# M_A_jumper_bed.net
KiCad netlist of a schematic drawn in EAGLE
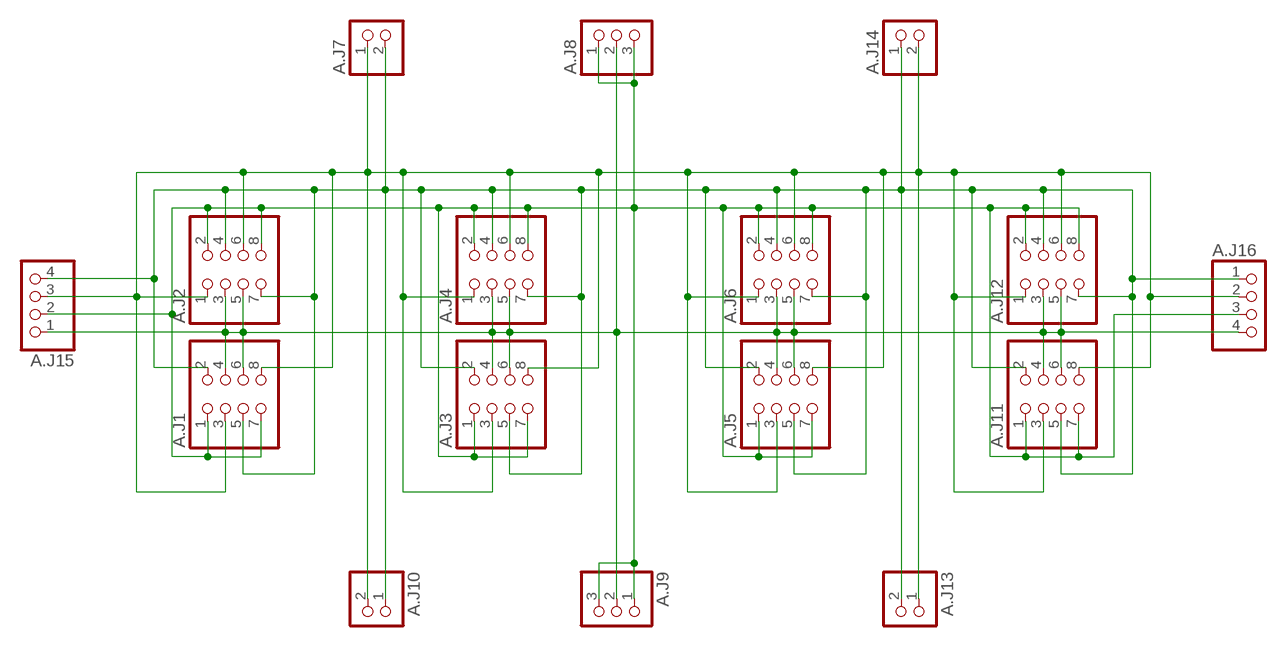
[diagram p0: schematic, sheet 1]

(export (version "E")
  (design (tool "Eeschema 10.0.6"))
  (components
    (comp (ref "A.J1")
      (value "PINHD-2X4")
      (footprint "eagle-import:2X04")
      (libsource (lib "eagle-import") (part "PINHD-2X4"))
    )
    (comp (ref "A.J2")
      (value "PINHD-2X4")
      (footprint "eagle-import:2X04")
      (libsource (lib "eagle-import") (part "PINHD-2X4"))
    )
    (comp (ref "A.J3")
      (value "PINHD-2X4")
      (footprint "eagle-import:2X04")
      (libsource (lib "eagle-import") (part "PINHD-2X4"))
    )
    (comp (ref "A.J4")
      (value "PINHD-2X4")
      (footprint "eagle-import:2X04")
      (libsource (lib "eagle-import") (part "PINHD-2X4"))
    )
    (comp (ref "A.J5")
      (value "PINHD-2X4")
      (footprint "eagle-import:2X04")
      (libsource (lib "eagle-import") (part "PINHD-2X4"))
    )
    (comp (ref "A.J6")
      (value "PINHD-2X4")
      (footprint "eagle-import:2X04")
      (libsource (lib "eagle-import") (part "PINHD-2X4"))
    )
    (comp (ref "A.J7")
      (value "PINHD-1X2/90")
      (footprint "eagle-import:1X02_90")
      (libsource (lib "eagle-import") (part "PINHD-1X2/90"))
    )
    (comp (ref "A.J8")
      (value "PINHD-1X3/90")
      (footprint "eagle-import:1X03_90")
      (libsource (lib "eagle-import") (part "PINHD-1X3/90"))
    )
    (comp (ref "A.J9")
      (value "PINHD-1X31X03/90F")
      (footprint "eagle-import:1X03_90F")
      (libsource (lib "eagle-import") (part "PINHD-1X31X03/90F"))
    )
    (comp (ref "A.J10")
      (value "PINHD-1X21X02/90F")
      (footprint "eagle-import:1X02_90F")
      (libsource (lib "eagle-import") (part "PINHD-1X21X02/90F"))
    )
    (comp (ref "A.J11")
      (value "PINHD-2X4")
      (footprint "eagle-import:2X04")
      (libsource (lib "eagle-import") (part "PINHD-2X4"))
    )
    (comp (ref "A.J12")
      (value "PINHD-2X4")
      (footprint "eagle-import:2X04")
      (libsource (lib "eagle-import") (part "PINHD-2X4"))
    )
    (comp (ref "A.J13")
      (value "PINHD-1X21X02/90F")
      (footprint "eagle-import:1X02_90F")
      (libsource (lib "eagle-import") (part "PINHD-1X21X02/90F"))
    )
    (comp (ref "A.J14")
      (value "PINHD-1X2/90")
      (footprint "eagle-import:1X02_90")
      (libsource (lib "eagle-import") (part "PINHD-1X2/90"))
    )
    (comp (ref "A.J15")
      (value "PINHD-1X4")
      (footprint "eagle-import:1X04")
      (libsource (lib "eagle-import") (part "PINHD-1X4"))
    )
    (comp (ref "A.J16")
      (value "PINHD-1X4")
      (footprint "eagle-import:1X04")
      (libsource (lib "eagle-import") (part "PINHD-1X4"))
    )
  )
  (nets
    (net (code "1") (name "Net-(A.J1-Pad1)") (class "Default")
      (node (ref "A.J1") (pin "1") (pinfunction "1_1") (pintype "passive"))
      (node (ref "A.J1") (pin "7") (pinfunction "7_7") (pintype "passive"))
      (node (ref "A.J11") (pin "1") (pinfunction "1_1") (pintype "passive"))
      (node (ref "A.J11") (pin "7") (pinfunction "7_7") (pintype "passive"))
      (node (ref "A.J12") (pin "2") (pinfunction "2_2") (pintype "passive"))
      (node (ref "A.J12") (pin "8") (pinfunction "8_8") (pintype "passive"))
      (node (ref "A.J15") (pin "2") (pinfunction "2_2") (pintype "passive"))
      (node (ref "A.J16") (pin "3") (pinfunction "3_3") (pintype "passive"))
      (node (ref "A.J2") (pin "2") (pinfunction "2_2") (pintype "passive"))
      (node (ref "A.J2") (pin "8") (pinfunction "8_8") (pintype "passive"))
      (node (ref "A.J3") (pin "1") (pinfunction "1_1") (pintype "passive"))
      (node (ref "A.J3") (pin "7") (pinfunction "7_7") (pintype "passive"))
      (node (ref "A.J4") (pin "2") (pinfunction "2_2") (pintype "passive"))
      (node (ref "A.J4") (pin "8") (pinfunction "8_8") (pintype "passive"))
      (node (ref "A.J5") (pin "1") (pinfunction "1_1") (pintype "passive"))
      (node (ref "A.J5") (pin "7") (pinfunction "7_7") (pintype "passive"))
      (node (ref "A.J6") (pin "2") (pinfunction "2_2") (pintype "passive"))
      (node (ref "A.J6") (pin "8") (pinfunction "8_8") (pintype "passive"))
      (node (ref "A.J8") (pin "1") (pinfunction "1_1") (pintype "passive"))
      (node (ref "A.J8") (pin "3") (pinfunction "3_3") (pintype "passive"))
      (node (ref "A.J9") (pin "1") (pinfunction "1_1") (pintype "passive"))
      (node (ref "A.J9") (pin "3") (pinfunction "3_3") (pintype "passive"))
    )
    (net (code "2") (name "Net-(A.J1-Pad2)") (class "Default")
      (node (ref "A.J1") (pin "2") (pinfunction "2_2") (pintype "passive"))
      (node (ref "A.J1") (pin "5") (pinfunction "5_5") (pintype "passive"))
      (node (ref "A.J10") (pin "1") (pinfunction "1_1") (pintype "passive"))
      (node (ref "A.J11") (pin "2") (pinfunction "2_2") (pintype "passive"))
      (node (ref "A.J11") (pin "5") (pinfunction "5_5") (pintype "passive"))
      (node (ref "A.J12") (pin "4") (pinfunction "4_4") (pintype "passive"))
      (node (ref "A.J12") (pin "7") (pinfunction "7_7") (pintype "passive"))
      (node (ref "A.J13") (pin "2") (pinfunction "2_2") (pintype "passive"))
      (node (ref "A.J14") (pin "1") (pinfunction "1_1") (pintype "passive"))
      (node (ref "A.J15") (pin "4") (pinfunction "4_4") (pintype "passive"))
      (node (ref "A.J16") (pin "1") (pinfunction "1_1") (pintype "passive"))
      (node (ref "A.J2") (pin "4") (pinfunction "4_4") (pintype "passive"))
      (node (ref "A.J2") (pin "7") (pinfunction "7_7") (pintype "passive"))
      (node (ref "A.J3") (pin "2") (pinfunction "2_2") (pintype "passive"))
      (node (ref "A.J3") (pin "5") (pinfunction "5_5") (pintype "passive"))
      (node (ref "A.J4") (pin "4") (pinfunction "4_4") (pintype "passive"))
      (node (ref "A.J4") (pin "7") (pinfunction "7_7") (pintype "passive"))
      (node (ref "A.J5") (pin "2") (pinfunction "2_2") (pintype "passive"))
      (node (ref "A.J5") (pin "5") (pinfunction "5_5") (pintype "passive"))
      (node (ref "A.J6") (pin "4") (pinfunction "4_4") (pintype "passive"))
      (node (ref "A.J6") (pin "7") (pinfunction "7_7") (pintype "passive"))
      (node (ref "A.J7") (pin "2") (pinfunction "2_2") (pintype "passive"))
    )
    (net (code "3") (name "Net-(A.J1-Pad3)") (class "Default")
      (node (ref "A.J1") (pin "3") (pinfunction "3_3") (pintype "passive"))
      (node (ref "A.J1") (pin "8") (pinfunction "8_8") (pintype "passive"))
      (node (ref "A.J10") (pin "2") (pinfunction "2_2") (pintype "passive"))
      (node (ref "A.J11") (pin "3") (pinfunction "3_3") (pintype "passive"))
      (node (ref "A.J11") (pin "8") (pinfunction "8_8") (pintype "passive"))
      (node (ref "A.J12") (pin "1") (pinfunction "1_1") (pintype "passive"))
      (node (ref "A.J12") (pin "6") (pinfunction "6_6") (pintype "passive"))
      (node (ref "A.J13") (pin "1") (pinfunction "1_1") (pintype "passive"))
      (node (ref "A.J14") (pin "2") (pinfunction "2_2") (pintype "passive"))
      (node (ref "A.J15") (pin "3") (pinfunction "3_3") (pintype "passive"))
      (node (ref "A.J16") (pin "2") (pinfunction "2_2") (pintype "passive"))
      (node (ref "A.J2") (pin "1") (pinfunction "1_1") (pintype "passive"))
      (node (ref "A.J2") (pin "6") (pinfunction "6_6") (pintype "passive"))
      (node (ref "A.J3") (pin "3") (pinfunction "3_3") (pintype "passive"))
      (node (ref "A.J3") (pin "8") (pinfunction "8_8") (pintype "passive"))
      (node (ref "A.J4") (pin "1") (pinfunction "1_1") (pintype "passive"))
      (node (ref "A.J4") (pin "6") (pinfunction "6_6") (pintype "passive"))
      (node (ref "A.J5") (pin "3") (pinfunction "3_3") (pintype "passive"))
      (node (ref "A.J5") (pin "8") (pinfunction "8_8") (pintype "passive"))
      (node (ref "A.J6") (pin "1") (pinfunction "1_1") (pintype "passive"))
      (node (ref "A.J6") (pin "6") (pinfunction "6_6") (pintype "passive"))
      (node (ref "A.J7") (pin "1") (pinfunction "1_1") (pintype "passive"))
    )
    (net (code "4") (name "Net-(A.J1-Pad4)") (class "Default")
      (node (ref "A.J1") (pin "4") (pinfunction "4_4") (pintype "passive"))
      (node (ref "A.J1") (pin "6") (pinfunction "6_6") (pintype "passive"))
      (node (ref "A.J11") (pin "4") (pinfunction "4_4") (pintype "passive"))
      (node (ref "A.J11") (pin "6") (pinfunction "6_6") (pintype "passive"))
      (node (ref "A.J12") (pin "3") (pinfunction "3_3") (pintype "passive"))
      (node (ref "A.J12") (pin "5") (pinfunction "5_5") (pintype "passive"))
      (node (ref "A.J15") (pin "1") (pinfunction "1_1") (pintype "passive"))
      (node (ref "A.J16") (pin "4") (pinfunction "4_4") (pintype "passive"))
      (node (ref "A.J2") (pin "3") (pinfunction "3_3") (pintype "passive"))
      (node (ref "A.J2") (pin "5") (pinfunction "5_5") (pintype "passive"))
      (node (ref "A.J3") (pin "4") (pinfunction "4_4") (pintype "passive"))
      (node (ref "A.J3") (pin "6") (pinfunction "6_6") (pintype "passive"))
      (node (ref "A.J4") (pin "3") (pinfunction "3_3") (pintype "passive"))
      (node (ref "A.J4") (pin "5") (pinfunction "5_5") (pintype "passive"))
      (node (ref "A.J5") (pin "4") (pinfunction "4_4") (pintype "passive"))
      (node (ref "A.J5") (pin "6") (pinfunction "6_6") (pintype "passive"))
      (node (ref "A.J6") (pin "3") (pinfunction "3_3") (pintype "passive"))
      (node (ref "A.J6") (pin "5") (pinfunction "5_5") (pintype "passive"))
      (node (ref "A.J8") (pin "2") (pinfunction "2_2") (pintype "passive"))
      (node (ref "A.J9") (pin "2") (pinfunction "2_2") (pintype "passive"))
    )
  )
)
